# Stepper.net
KiCad netlist of a schematic drawn in Altium Designer
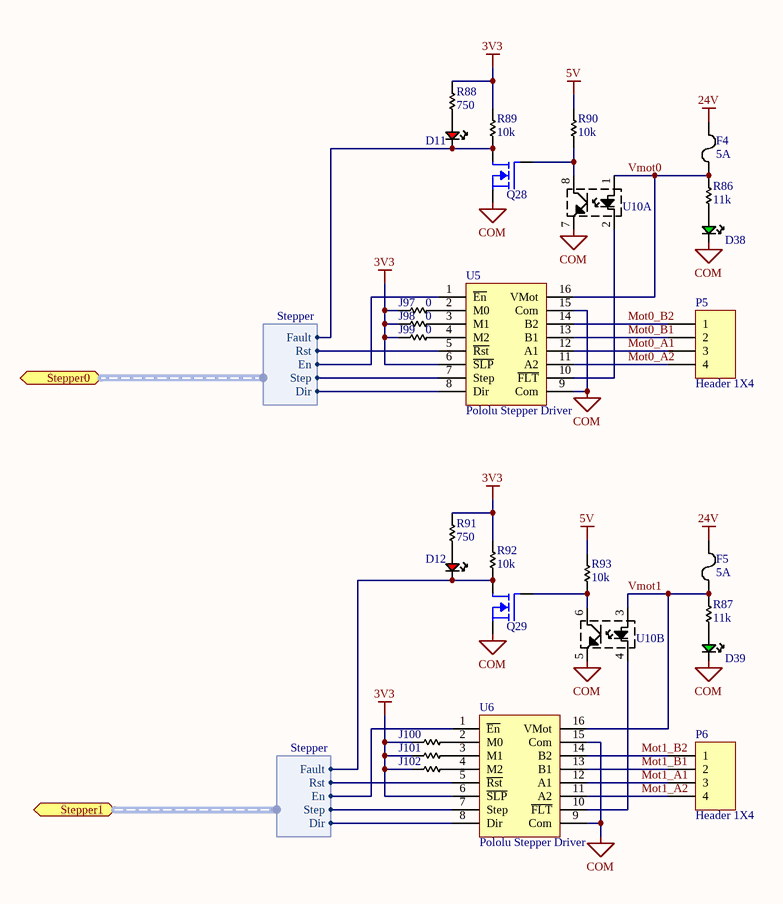
[diagram p0: Stepper.SchDoc]

(export (version "E")
  (design (tool "Eeschema 10.0.6"))
  (components
    (comp (ref "D11")
      (value "Red")
      (footprint "0805 - Led Red")
      (description "LED 630NM RED WTR CLR 0805 SMD")
      (fields
        (field (name "PART NUMBER") "LED-Red-2mA-lowBrigthness-0805")
        (field (name "MANUFACTURER") "Rohm semiconductor")
        (field (name "CREATED BY") "Pier-Yves")
      )
      (libsource (lib "local") (part "Led Red"))
    )
    (comp (ref "D12")
      (value "Red")
      (footprint "0805 - Led Red")
      (description "LED 630NM RED WTR CLR 0805 SMD")
      (fields
        (field (name "PART NUMBER") "LED-Red-2mA-lowBrigthness-0805")
        (field (name "MANUFACTURER") "Rohm semiconductor")
        (field (name "CREATED BY") "Pier-Yves")
      )
      (libsource (lib "local") (part "Led Red"))
    )
    (comp (ref "D38")
      (value "Green")
      (footprint "0603 - Led Green")
      (description "LED SMARTLED GREEN 570NM 0603")
      (fields
        (field (name "PART NUMBER") "LED-Green-2mA-lowBrigthness-0603")
        (field (name "MANUFACTURER") "OSRAM Opto Semiconductor")
        (field (name "CREATED BY") "Pier-Yves")
      )
      (libsource (lib "local") (part "Led Green"))
    )
    (comp (ref "D39")
      (value "Green")
      (footprint "0603 - Led Green")
      (description "LED SMARTLED GREEN 570NM 0603")
      (fields
        (field (name "PART NUMBER") "LED-Green-2mA-lowBrigthness-0603")
        (field (name "MANUFACTURER") "OSRAM Opto Semiconductor")
        (field (name "CREATED BY") "Pier-Yves")
      )
      (libsource (lib "local") (part "Led Green"))
    )
    (comp (ref "F4")
      (value "5A")
      (footprint "Fuse - 1206")
      (description "FUSE SLOW 24VDC 5A 1206")
      (fields
        (field (name "PART NUMBER") "Fuse-1206-Bourns-Slow-SinglFuse_SF-1206S-5A")
        (field (name "MANUFACTURER") "Bourns Inc.")
        (field (name "CREATED BY") "Pier-Yves")
      )
      (libsource (lib "local") (part "Fuse"))
    )
    (comp (ref "F5")
      (value "5A")
      (footprint "Fuse - 1206")
      (description "FUSE SLOW 24VDC 5A 1206")
      (fields
        (field (name "PART NUMBER") "Fuse-1206-Bourns-Slow-SinglFuse_SF-1206S-5A")
        (field (name "MANUFACTURER") "Bourns Inc.")
        (field (name "CREATED BY") "Pier-Yves")
      )
      (libsource (lib "local") (part "Fuse"))
    )
    (comp (ref "J97")
      (value "0")
      (footprint "0805 - Resistor")
      (description "RES 0.0 OHM 1/8W JUMP 0805")
      (fields
        (field (name "PART NUMBER") "Jumper-0805")
        (field (name "MANUFACTURER") "Stackpole electronic")
        (field (name "CREATED BY") "Pier-Yves")
      )
      (libsource (lib "local") (part "Res"))
    )
    (comp (ref "J98")
      (value "0")
      (footprint "0805 - Resistor")
      (description "RES 0.0 OHM 1/8W JUMP 0805")
      (fields
        (field (name "PART NUMBER") "Jumper-0805")
        (field (name "MANUFACTURER") "Stackpole electronic")
        (field (name "CREATED BY") "Pier-Yves")
      )
      (libsource (lib "local") (part "Res"))
    )
    (comp (ref "J99")
      (value "0")
      (footprint "0805 - Resistor")
      (description "RES 0.0 OHM 1/8W JUMP 0805")
      (fields
        (field (name "PART NUMBER") "Jumper-0805")
        (field (name "MANUFACTURER") "Stackpole electronic")
        (field (name "CREATED BY") "Pier-Yves")
      )
      (libsource (lib "local") (part "Res"))
    )
    (comp (ref "J100")
      (value "Res")
      (footprint "0805 - Resistor")
      (description "RES 0.0 OHM 1/8W JUMP 0805")
      (fields
        (field (name "PART NUMBER") "Jumper-0805")
        (field (name "MANUFACTURER") "Stackpole electronic")
        (field (name "CREATED BY") "Pier-Yves")
      )
      (libsource (lib "local") (part "Res"))
    )
    (comp (ref "J101")
      (value "Res")
      (footprint "0805 - Resistor")
      (description "RES 0.0 OHM 1/8W JUMP 0805")
      (fields
        (field (name "PART NUMBER") "Jumper-0805")
        (field (name "MANUFACTURER") "Stackpole electronic")
        (field (name "CREATED BY") "Pier-Yves")
      )
      (libsource (lib "local") (part "Res"))
    )
    (comp (ref "J102")
      (value "Res")
      (footprint "0805 - Resistor")
      (description "RES 0.0 OHM 1/8W JUMP 0805")
      (fields
        (field (name "PART NUMBER") "Jumper-0805")
        (field (name "MANUFACTURER") "Stackpole electronic")
        (field (name "CREATED BY") "Pier-Yves")
      )
      (libsource (lib "local") (part "Res"))
    )
    (comp (ref "P5")
      (value "Header 1X4")
      (footprint "Headers - 1x4 - Vertical - Lock")
      (description "CONN HEADER 4POS .100\" STR TIN")
      (fields
        (field (name "PART NUMBER") "Header-0.100-Vertical-Lock-1X4")
        (field (name "MANUFACTURER") "Molex Inc")
        (field (name "PUBLISHER") "Altium Limited")
        (field (name "CREATED BY") "Pier-Yves")
      )
      (libsource (lib "local") (part "Header 1X4"))
    )
    (comp (ref "P6")
      (value "Header 1X4")
      (footprint "Headers - 1x4 - Vertical - Lock")
      (description "CONN HEADER 4POS .100\" STR TIN")
      (fields
        (field (name "PART NUMBER") "Header-0.100-Vertical-Lock-1X4")
        (field (name "MANUFACTURER") "Molex Inc")
        (field (name "PUBLISHER") "Altium Limited")
        (field (name "CREATED BY") "Pier-Yves")
      )
      (libsource (lib "local") (part "Header 1X4"))
    )
    (comp (ref "Q28")
      (value "MOSFET_N")
      (footprint "SOT23-3")
      (description "MosFET Channel-N SOT-23-3 3.3A")
      (fields
        (field (name "PART NUMBER") "2N7002")
        (field (name "MANUFACTURER") "Vishay Siliconix")
        (field (name "CREATED BY") "Pier-Yves")
      )
      (libsource (lib "local") (part "MOSFET_N_GSD"))
    )
    (comp (ref "Q29")
      (value "MOSFET_N")
      (footprint "SOT23-3")
      (description "MosFET Channel-N SOT-23-3 3.3A")
      (fields
        (field (name "PART NUMBER") "2N7002")
        (field (name "MANUFACTURER") "Vishay Siliconix")
        (field (name "CREATED BY") "Pier-Yves")
      )
      (libsource (lib "local") (part "MOSFET_N_GSD"))
    )
    (comp (ref "R86")
      (value "11k")
      (footprint "0805 - Resistor")
      (description "RES 11K OHM 1/8W 5% 0805 SMD")
      (fields
        (field (name "PART NUMBER") "Yagao-RC0805-11k")
        (field (name "MANUFACTURER") "Yagao")
        (field (name "CREATED BY") "Pier-Yves")
      )
      (libsource (lib "local") (part "Res"))
    )
    (comp (ref "R87")
      (value "11k")
      (footprint "0805 - Resistor")
      (description "RES 11K OHM 1/8W 5% 0805 SMD")
      (fields
        (field (name "PART NUMBER") "Yagao-RC0805-11k")
        (field (name "MANUFACTURER") "Yagao")
        (field (name "CREATED BY") "Pier-Yves")
      )
      (libsource (lib "local") (part "Res"))
    )
    (comp (ref "R88")
      (value "750")
      (footprint "0805 - Resistor")
      (description "RES 750 OHM 1/8W 5% 0805 SMD")
      (fields
        (field (name "PART NUMBER") "Yagao-RC0805-750")
        (field (name "MANUFACTURER") "Yagao")
        (field (name "CREATED BY") "Pier-Yves")
      )
      (libsource (lib "local") (part "Res"))
    )
    (comp (ref "R89")
      (value "10k")
      (footprint "0805 - Resistor")
      (description "RES 10K OHM 1/8W 5% 0805 SMD")
      (fields
        (field (name "PART NUMBER") "Yagao-RC0805-10k")
        (field (name "MANUFACTURER") "Yagao")
        (field (name "CREATED BY") "Pier-Yves")
      )
      (libsource (lib "local") (part "Res"))
    )
    (comp (ref "R90")
      (value "10k")
      (footprint "0805 - Resistor")
      (description "RES 10K OHM 1/8W 5% 0805 SMD")
      (fields
        (field (name "PART NUMBER") "Yagao-RC0805-10k")
        (field (name "MANUFACTURER") "Yagao")
        (field (name "CREATED BY") "Pier-Yves")
      )
      (libsource (lib "local") (part "Res"))
    )
    (comp (ref "R91")
      (value "750")
      (footprint "0805 - Resistor")
      (description "RES 750 OHM 1/8W 5% 0805 SMD")
      (fields
        (field (name "PART NUMBER") "Yagao-RC0805-750")
        (field (name "MANUFACTURER") "Yagao")
        (field (name "CREATED BY") "Pier-Yves")
      )
      (libsource (lib "local") (part "Res"))
    )
    (comp (ref "R92")
      (value "10k")
      (footprint "0805 - Resistor")
      (description "RES 10K OHM 1/8W 5% 0805 SMD")
      (fields
        (field (name "PART NUMBER") "Yagao-RC0805-10k")
        (field (name "MANUFACTURER") "Yagao")
        (field (name "CREATED BY") "Pier-Yves")
      )
      (libsource (lib "local") (part "Res"))
    )
    (comp (ref "R93")
      (value "10k")
      (footprint "0805 - Resistor")
      (description "RES 10K OHM 1/8W 5% 0805 SMD")
      (fields
        (field (name "PART NUMBER") "Yagao-RC0805-10k")
        (field (name "MANUFACTURER") "Yagao")
        (field (name "CREATED BY") "Pier-Yves")
      )
      (libsource (lib "local") (part "Res"))
    )
    (comp (ref "U5")
      (value "Pololu Stepper Driver")
      (footprint "Pololu - DRV8825 - socket")
      (description "Pololu 4 phase stepper driver 1/32 step")
      (fields
        (field (name "PART NUMBER") "Pololu-DRV8825-BiPolar-HighCurrent")
        (field (name "MANUFACTURER") "Pololu")
        (field (name "CREATED BY") "Pier-Yves")
      )
      (libsource (lib "local") (part "Pololu - DRV8825"))
    )
    (comp (ref "U6")
      (value "Pololu Stepper Driver")
      (footprint "Pololu - DRV8825 - socket")
      (description "Pololu 4 phase stepper driver 1/32 step")
      (fields
        (field (name "PART NUMBER") "Pololu-DRV8825-BiPolar-HighCurrent")
        (field (name "MANUFACTURER") "Pololu")
        (field (name "CREATED BY") "Pier-Yves")
      )
      (libsource (lib "local") (part "Pololu - DRV8825"))
    )
    (comp (ref "U10")
      (value "LTV-827S-TA1")
      (footprint "8-SMD - GullWing")
      (description "OPTOCOUPLER TRANS 5KVRMS 8SMD")
      (fields
        (field (name "MANUFACTURER") "Lite-On")
        (field (name "POWER") "2ch")
        (field (name "CREATED BY") "Pier-Yves")
      )
      (libsource (lib "local") (part "LTV-827S-TA1"))
    )
  )
  (nets
    (net (code "2") (name "/Mot0_A1") (class "Default")
      (node (ref "P5") (pin "3") (pinfunction "3_3") (pintype "passive"))
      (node (ref "U5") (pin "12") (pinfunction "A1_12") (pintype "passive"))
    )
    (net (code "3") (name "/Mot0_A2") (class "Default")
      (node (ref "P5") (pin "4") (pinfunction "4_4") (pintype "passive"))
      (node (ref "U5") (pin "11") (pinfunction "A2_11") (pintype "passive"))
    )
    (net (code "4") (name "/Mot0_B1") (class "Default")
      (node (ref "P5") (pin "2") (pinfunction "2_2") (pintype "passive"))
      (node (ref "U5") (pin "13") (pinfunction "B1_13") (pintype "passive"))
    )
    (net (code "5") (name "/Mot0_B2") (class "Default")
      (node (ref "P5") (pin "1") (pinfunction "1_1") (pintype "passive"))
      (node (ref "U5") (pin "14") (pinfunction "B2_14") (pintype "passive"))
    )
    (net (code "6") (name "/Mot1_A1") (class "Default")
      (node (ref "P6") (pin "3") (pinfunction "3_3") (pintype "passive"))
      (node (ref "U6") (pin "12") (pinfunction "A1_12") (pintype "passive"))
    )
    (net (code "7") (name "/Mot1_A2") (class "Default")
      (node (ref "P6") (pin "4") (pinfunction "4_4") (pintype "passive"))
      (node (ref "U6") (pin "11") (pinfunction "A2_11") (pintype "passive"))
    )
    (net (code "8") (name "/Mot1_B1") (class "Default")
      (node (ref "P6") (pin "2") (pinfunction "2_2") (pintype "passive"))
      (node (ref "U6") (pin "13") (pinfunction "B1_13") (pintype "passive"))
    )
    (net (code "9") (name "/Mot1_B2") (class "Default")
      (node (ref "P6") (pin "1") (pinfunction "1_1") (pintype "passive"))
      (node (ref "U6") (pin "14") (pinfunction "B2_14") (pintype "passive"))
    )
    (net (code "10") (name "/Vmot0") (class "Default")
      (node (ref "F4") (pin "2") (pinfunction "2_2") (pintype "passive"))
      (node (ref "R86") (pin "2") (pinfunction "2_2") (pintype "passive"))
      (node (ref "U10") (pin "1") (pinfunction "A1_1") (pintype "passive"))
      (node (ref "U5") (pin "16") (pinfunction "VMot_16") (pintype "passive"))
    )
    (net (code "11") (name "/Vmot1") (class "Default")
      (node (ref "F5") (pin "2") (pinfunction "2_2") (pintype "passive"))
      (node (ref "R87") (pin "2") (pinfunction "2_2") (pintype "passive"))
      (node (ref "U10") (pin "3") (pinfunction "A2_3") (pintype "passive"))
      (node (ref "U6") (pin "16") (pinfunction "VMot_16") (pintype "passive"))
    )
    (net (code "13") (name "3V3") (class "Default")
      (node (ref "J100") (pin "2") (pinfunction "2_2") (pintype "passive"))
      (node (ref "J101") (pin "2") (pinfunction "2_2") (pintype "passive"))
      (node (ref "J102") (pin "2") (pinfunction "2_2") (pintype "passive"))
      (node (ref "J97") (pin "2") (pinfunction "2_2") (pintype "passive"))
      (node (ref "J98") (pin "2") (pinfunction "2_2") (pintype "passive"))
      (node (ref "J99") (pin "2") (pinfunction "2_2") (pintype "passive"))
      (node (ref "R88") (pin "2") (pinfunction "2_2") (pintype "passive"))
      (node (ref "R89") (pin "1") (pinfunction "1_1") (pintype "passive"))
      (node (ref "R91") (pin "2") (pinfunction "2_2") (pintype "passive"))
      (node (ref "R92") (pin "1") (pinfunction "1_1") (pintype "passive"))
      (node (ref "U5") (pin "6") (pinfunction "~{SLP}_6") (pintype "passive"))
      (node (ref "U6") (pin "6") (pinfunction "~{SLP}_6") (pintype "passive"))
    )
    (net (code "14") (name "5V") (class "Default")
      (node (ref "R90") (pin "1") (pinfunction "1_1") (pintype "passive"))
      (node (ref "R93") (pin "1") (pinfunction "1_1") (pintype "passive"))
    )
    (net (code "15") (name "24V") (class "Default")
      (node (ref "F4") (pin "1") (pinfunction "1_1") (pintype "passive"))
      (node (ref "F5") (pin "1") (pinfunction "1_1") (pintype "passive"))
    )
    (net (code "16") (name "COM") (class "Default")
      (node (ref "D38") (pin "2") (pinfunction "K_2") (pintype "passive"))
      (node (ref "D39") (pin "2") (pinfunction "K_2") (pintype "passive"))
      (node (ref "Q28") (pin "2") (pinfunction "S_2") (pintype "passive"))
      (node (ref "Q29") (pin "2") (pinfunction "S_2") (pintype "passive"))
      (node (ref "U10") (pin "5") (pinfunction "E2_5") (pintype "passive"))
      (node (ref "U10") (pin "7") (pinfunction "E1_7") (pintype "passive"))
      (node (ref "U5") (pin "15") (pinfunction "Com_15") (pintype "passive"))
      (node (ref "U5") (pin "9") (pinfunction "Com_9") (pintype "passive"))
      (node (ref "U6") (pin "15") (pinfunction "Com_15") (pintype "passive"))
      (node (ref "U6") (pin "9") (pinfunction "Com_9") (pintype "passive"))
    )
    (net (code "17") (name "Net-(D11-A)") (class "Default")
      (node (ref "D11") (pin "1") (pinfunction "A_1") (pintype "passive"))
      (node (ref "R88") (pin "1") (pinfunction "1_1") (pintype "passive"))
    )
    (net (code "18") (name "Net-(D11-K)") (class "Default")
      (node (ref "D11") (pin "2") (pinfunction "K_2") (pintype "passive"))
      (node (ref "Q28") (pin "3") (pinfunction "D_3") (pintype "passive"))
      (node (ref "R89") (pin "2") (pinfunction "2_2") (pintype "passive"))
    )
    (net (code "19") (name "Net-(D12-A)") (class "Default")
      (node (ref "D12") (pin "1") (pinfunction "A_1") (pintype "passive"))
      (node (ref "R91") (pin "1") (pinfunction "1_1") (pintype "passive"))
    )
    (net (code "20") (name "Net-(D12-K)") (class "Default")
      (node (ref "D12") (pin "2") (pinfunction "K_2") (pintype "passive"))
      (node (ref "Q29") (pin "3") (pinfunction "D_3") (pintype "passive"))
      (node (ref "R92") (pin "2") (pinfunction "2_2") (pintype "passive"))
    )
    (net (code "21") (name "Net-(D38-A)") (class "Default")
      (node (ref "D38") (pin "1") (pinfunction "A_1") (pintype "passive"))
      (node (ref "R86") (pin "1") (pinfunction "1_1") (pintype "passive"))
    )
    (net (code "22") (name "Net-(D39-A)") (class "Default")
      (node (ref "D39") (pin "1") (pinfunction "A_1") (pintype "passive"))
      (node (ref "R87") (pin "1") (pinfunction "1_1") (pintype "passive"))
    )
    (net (code "23") (name "Net-(Q28-G)") (class "Default")
      (node (ref "Q28") (pin "1") (pinfunction "G_1") (pintype "passive"))
      (node (ref "R90") (pin "2") (pinfunction "2_2") (pintype "passive"))
      (node (ref "U10") (pin "8") (pinfunction "C1_8") (pintype "passive"))
    )
    (net (code "24") (name "Net-(Q29-G)") (class "Default")
      (node (ref "Q29") (pin "1") (pinfunction "G_1") (pintype "passive"))
      (node (ref "R93") (pin "2") (pinfunction "2_2") (pintype "passive"))
      (node (ref "U10") (pin "6") (pinfunction "C2_6") (pintype "passive"))
    )
    (net (code "25") (name "Net-(U5-M0)") (class "Default")
      (node (ref "J97") (pin "1") (pinfunction "1_1") (pintype "passive"))
      (node (ref "U5") (pin "2") (pinfunction "M0_2") (pintype "passive"))
    )
    (net (code "26") (name "Net-(U5-M1)") (class "Default")
      (node (ref "J98") (pin "1") (pinfunction "1_1") (pintype "passive"))
      (node (ref "U5") (pin "3") (pinfunction "M1_3") (pintype "passive"))
    )
    (net (code "27") (name "Net-(U5-M2)") (class "Default")
      (node (ref "J99") (pin "1") (pinfunction "1_1") (pintype "passive"))
      (node (ref "U5") (pin "4") (pinfunction "M2_4") (pintype "passive"))
    )
    (net (code "28") (name "Net-(U6-M0)") (class "Default")
      (node (ref "J100") (pin "1") (pinfunction "1_1") (pintype "passive"))
      (node (ref "U6") (pin "2") (pinfunction "M0_2") (pintype "passive"))
    )
    (net (code "29") (name "Net-(U6-M1)") (class "Default")
      (node (ref "J101") (pin "1") (pinfunction "1_1") (pintype "passive"))
      (node (ref "U6") (pin "3") (pinfunction "M1_3") (pintype "passive"))
    )
    (net (code "30") (name "Net-(U6-M2)") (class "Default")
      (node (ref "J102") (pin "1") (pinfunction "1_1") (pintype "passive"))
      (node (ref "U6") (pin "4") (pinfunction "M2_4") (pintype "passive"))
    )
    (net (code "31") (name "Net-(U10A-K1)") (class "Default")
      (node (ref "U10") (pin "2") (pinfunction "K1_2") (pintype "passive"))
      (node (ref "U5") (pin "10") (pinfunction "~{FLT}_10") (pintype "passive"))
    )
    (net (code "32") (name "Net-(U10B-K2)") (class "Default")
      (node (ref "U10") (pin "4") (pinfunction "K2_4") (pintype "passive"))
      (node (ref "U6") (pin "10") (pinfunction "~{FLT}_10") (pintype "passive"))
    )
    (net (code "33") (name "unconnected-(U5-Dir-Pad8)") (class "Default")
      (node (ref "U5") (pin "8") (pinfunction "Dir_8") (pintype "passive"))
    )
    (net (code "34") (name "unconnected-(U5-Step-Pad7)") (class "Default")
      (node (ref "U5") (pin "7") (pinfunction "Step_7") (pintype "passive"))
    )
    (net (code "35") (name "unconnected-(U5-~{En}-Pad1)") (class "Default")
      (node (ref "U5") (pin "1") (pinfunction "~{En}_1") (pintype "passive"))
    )
    (net (code "36") (name "unconnected-(U5-~{Rst}-Pad5)") (class "Default")
      (node (ref "U5") (pin "5") (pinfunction "~{Rst}_5") (pintype "passive"))
    )
    (net (code "37") (name "unconnected-(U6-Dir-Pad8)") (class "Default")
      (node (ref "U6") (pin "8") (pinfunction "Dir_8") (pintype "passive"))
    )
    (net (code "38") (name "unconnected-(U6-Step-Pad7)") (class "Default")
      (node (ref "U6") (pin "7") (pinfunction "Step_7") (pintype "passive"))
    )
    (net (code "39") (name "unconnected-(U6-~{En}-Pad1)") (class "Default")
      (node (ref "U6") (pin "1") (pinfunction "~{En}_1") (pintype "passive"))
    )
    (net (code "40") (name "unconnected-(U6-~{Rst}-Pad5)") (class "Default")
      (node (ref "U6") (pin "5") (pinfunction "~{Rst}_5") (pintype "passive"))
    )
  )
)
